# SCH_WHITEBoard_ESP32_S2_Saola_2021-06-30.net
KiCad netlist of a schematic drawn in EasyEDA
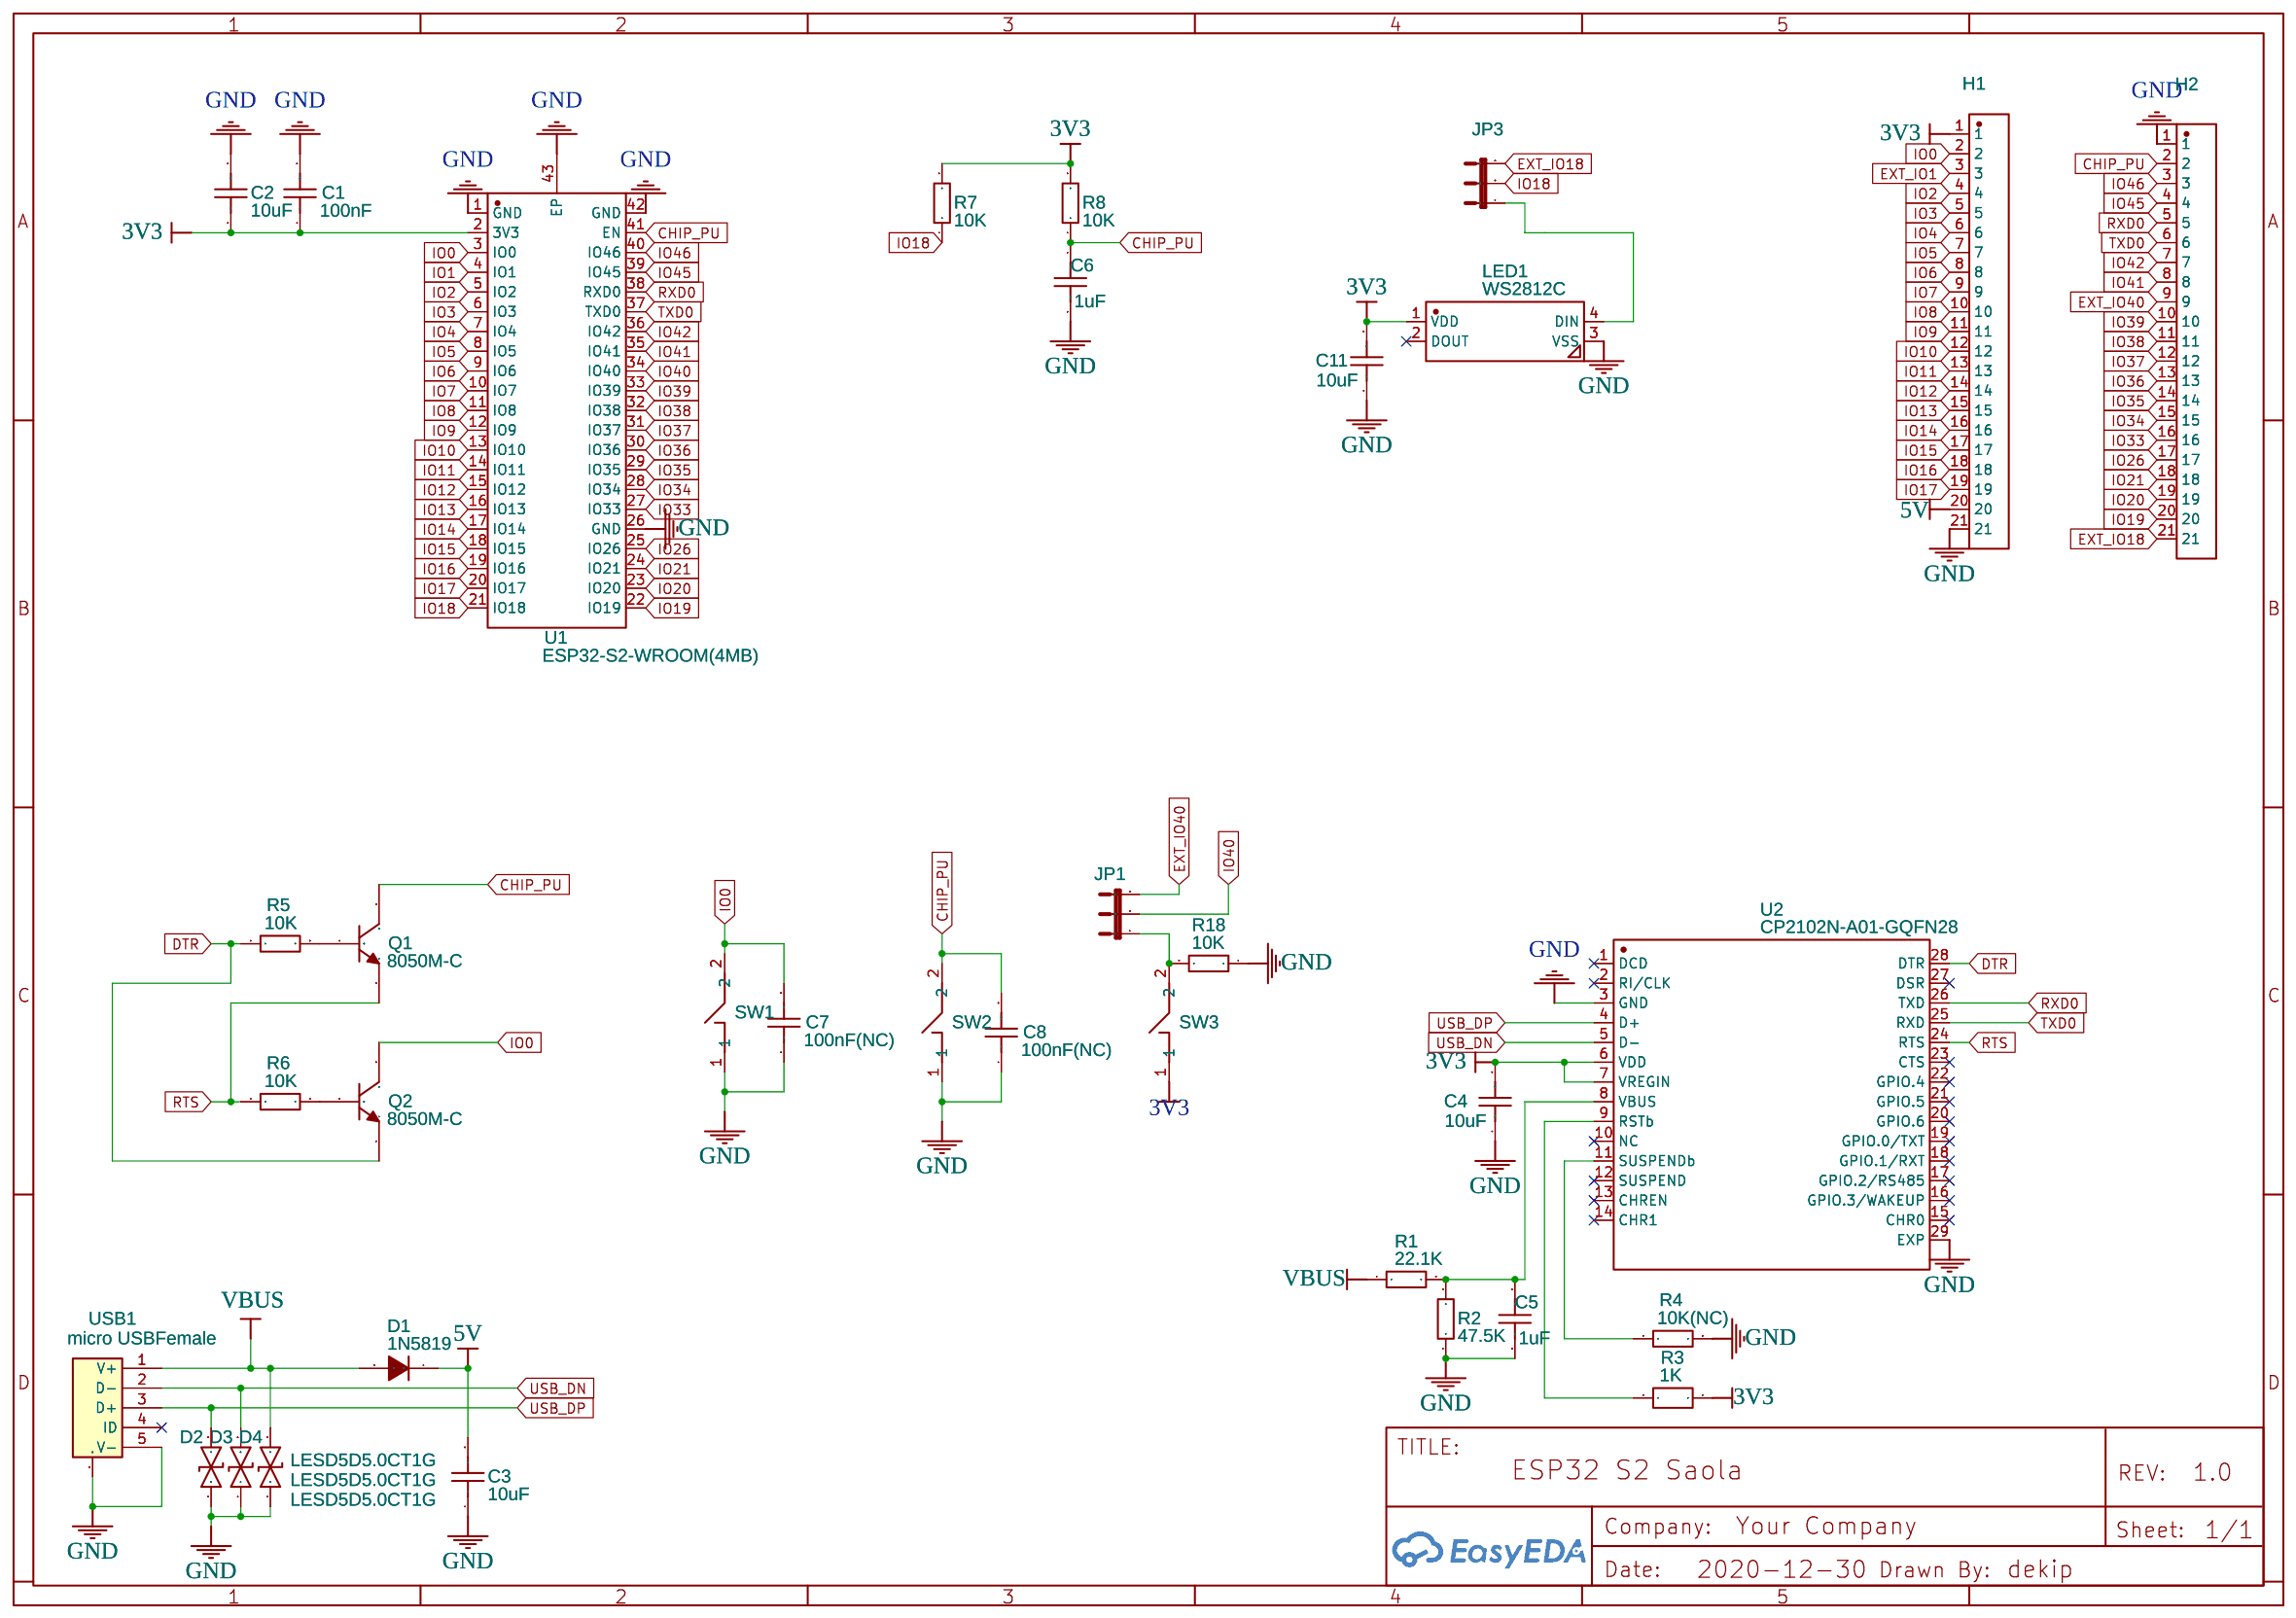
[diagram p0: Sheet_1]
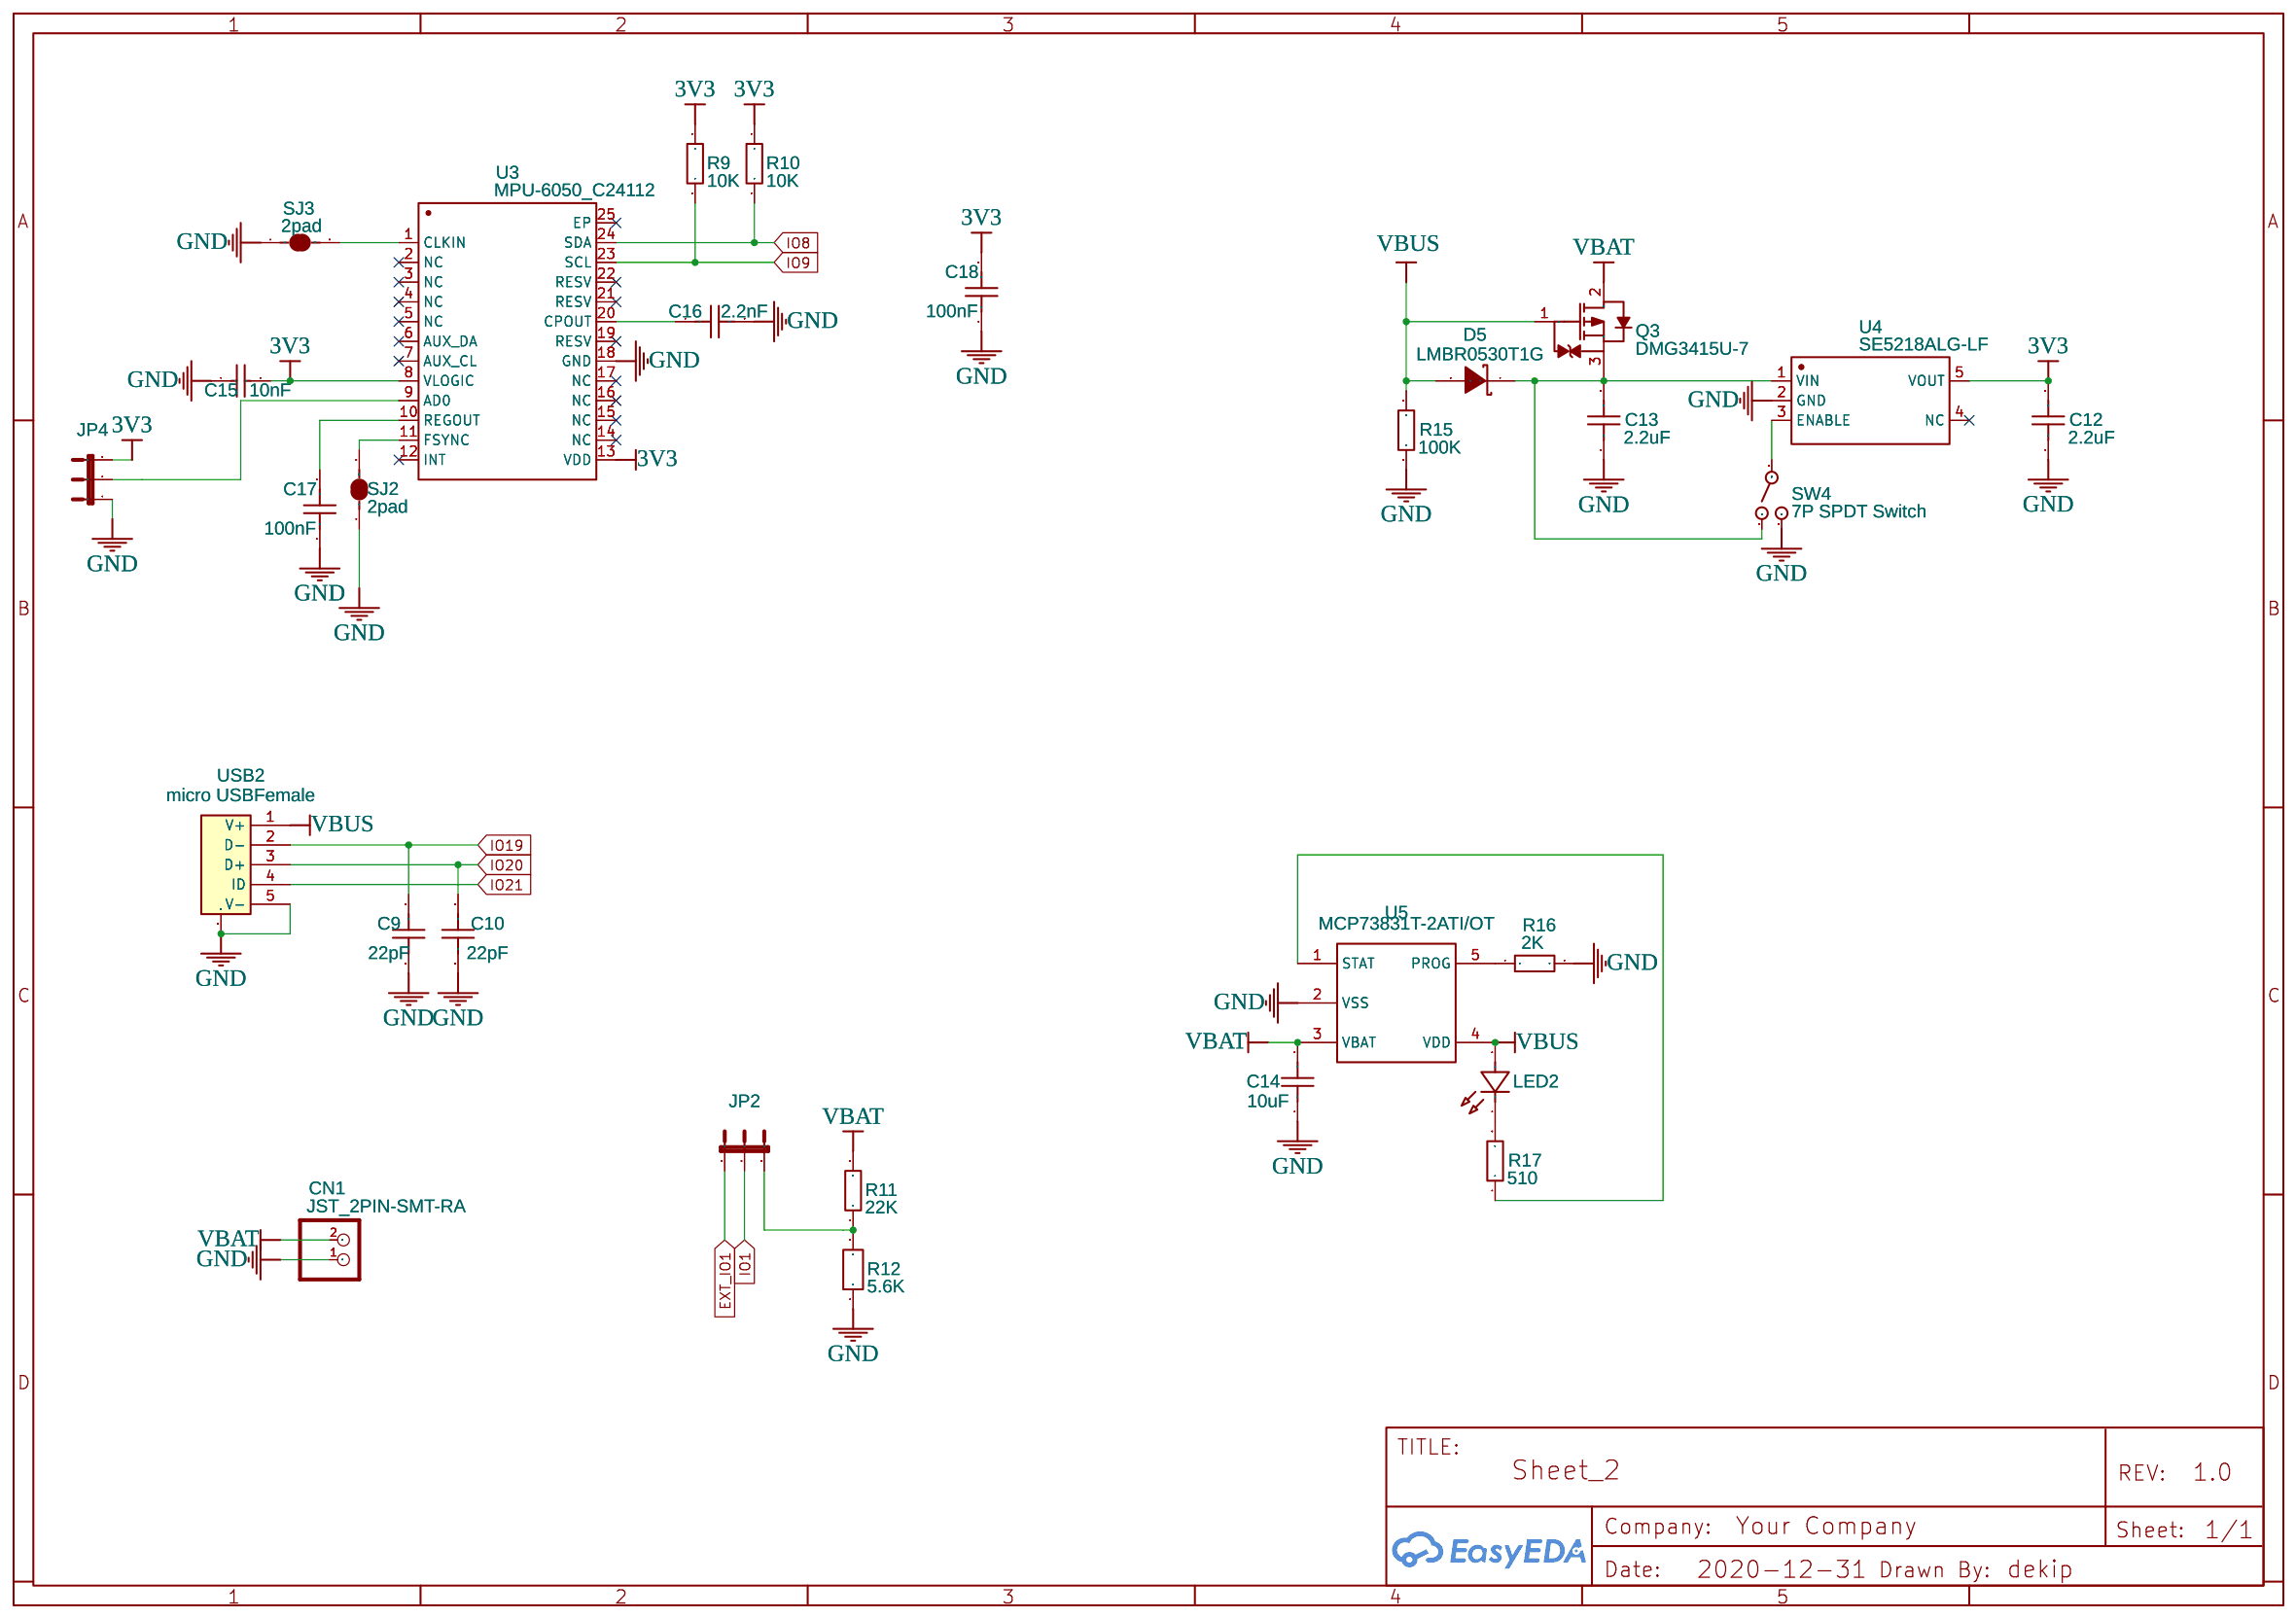
[diagram p1: Sheet_2]

(export (version "E")
  (design (tool "Eeschema 10.0.6"))
  (components
    (comp (ref "C1")
      (value "100nF")
      (fields
        (field (name "BOM_Manufacturer Part") "C0805C104J5RAC7800")
        (field (name "BOM_Supplier Part") "C599848")
      )
      (libsource (lib "") (part "C0805C104J5RAC7800"))
    )
    (comp (ref "C2")
      (value "10uF")
      (fields
        (field (name "BOM_Manufacturer Part") "C0805X106K010T")
        (field (name "BOM_Supplier Part") "C340314")
      )
      (libsource (lib "") (part "C0805X106K010T"))
    )
    (comp (ref "C3")
      (value "10uF")
      (fields
        (field (name "BOM_Manufacturer Part") "C0805X106K010T")
        (field (name "BOM_Supplier Part") "C340314")
      )
      (libsource (lib "") (part "C0805X106K010T"))
    )
    (comp (ref "C4")
      (value "10uF")
      (fields
        (field (name "BOM_Manufacturer Part") "C0805X106K010T")
        (field (name "BOM_Supplier Part") "C340314")
      )
      (libsource (lib "") (part "C0805X106K010T"))
    )
    (comp (ref "C5")
      (value "1uF")
      (fields
        (field (name "BOM_Manufacturer Part") "C0805X105K050T")
        (field (name "BOM_Supplier Part") "C340303")
      )
      (libsource (lib "") (part "C0805X105K050T"))
    )
    (comp (ref "C6")
      (value "1uF")
      (fields
        (field (name "BOM_Manufacturer Part") "C0805X105K050T")
        (field (name "BOM_Supplier Part") "C340303")
      )
      (libsource (lib "") (part "C0805X105K050T"))
    )
    (comp (ref "C7")
      (value "100nF(NC)")
      (fields
        (field (name "BOM_Manufacturer Part") "C0805C104J5RAC7800")
        (field (name "BOM_Supplier Part") "C599848")
      )
      (libsource (lib "") (part "C0805C104J5RAC7800"))
    )
    (comp (ref "C8")
      (value "100nF(NC)")
      (fields
        (field (name "BOM_Manufacturer Part") "C0805C104J5RAC7800")
        (field (name "BOM_Supplier Part") "C599848")
      )
      (libsource (lib "") (part "C0805C104J5RAC7800"))
    )
    (comp (ref "C11")
      (value "10uF")
      (fields
        (field (name "BOM_Manufacturer Part") "C0805X106K010T")
        (field (name "BOM_Supplier Part") "C340314")
      )
      (libsource (lib "") (part "C0805X106K010T"))
    )
    (comp (ref "D1")
      (value "1N5819")
      (fields
        (field (name "BOM_Manufacturer Part") "1N5819HW1-7-F")
        (field (name "BOM_Supplier Part") "C117948")
      )
      (libsource (lib "") (part "1N5819HW1-7-F"))
    )
    (comp (ref "D2")
      (value "LESD5D5.0CT1G")
      (fields (field (name "BOM_Supplier Part") "C383211"))
      (libsource (lib "") (part "LESD5D5.0CT1G"))
    )
    (comp (ref "D3")
      (value "LESD5D5.0CT1G")
      (fields (field (name "BOM_Supplier Part") "C383211"))
      (libsource (lib "") (part "LESD5D5.0CT1G"))
    )
    (comp (ref "D4")
      (value "LESD5D5.0CT1G")
      (fields (field (name "BOM_Supplier Part") "C383211"))
      (libsource (lib "") (part "LESD5D5.0CT1G"))
    )
    (comp (ref "H1")
      (value "X6511WV-21H-C30D60")
      (fields (field (name "BOM_Supplier Part") "C725953"))
      (libsource (lib "") (part "X6511WV-21H-C30D60"))
    )
    (comp (ref "H2")
      (value "X6511WV-21H-C30D60")
      (fields (field (name "BOM_Supplier Part") "C725953"))
      (libsource (lib "") (part "X6511WV-21H-C30D60"))
    )
    (comp (ref "JP1") (value "JUMPER-3SMD") (libsource (lib "") (part "JUMPER-3SMD")))
    (comp (ref "JP3") (value "JUMPER-3SMD") (libsource (lib "") (part "JUMPER-3SMD")))
    (comp (ref "LED1")
      (value "WS2812C")
      (fields (field (name "BOM_Supplier Part") "C114587"))
      (libsource (lib "") (part "WS2812C"))
    )
    (comp (ref "Q1")
      (value "8050M-C")
      (fields (field (name "BOM_Supplier Part") "C305454"))
      (libsource (lib "") (part "8050M-C"))
    )
    (comp (ref "Q2")
      (value "8050M-C")
      (fields (field (name "BOM_Supplier Part") "C305454"))
      (libsource (lib "") (part "8050M-C"))
    )
    (comp (ref "R1")
      (value "22.1K")
      (fields
        (field (name "BOM_Manufacturer Part") "CR0805-FX-2212ELF")
        (field (name "BOM_Supplier Part") "C204311")
      )
      (libsource (lib "") (part "CR0805-FX-2212ELF"))
    )
    (comp (ref "R2")
      (value "47.5K")
      (fields
        (field (name "BOM_Manufacturer Part") "AR05DTCW4752")
        (field (name "BOM_Supplier Part") "C319613")
      )
      (libsource (lib "") (part "AR05DTCW4752"))
    )
    (comp (ref "R3")
      (value "1K")
      (fields
        (field (name "BOM_Manufacturer Part") "ERJPB6B1001V")
        (field (name "BOM_Supplier Part") "C413712")
      )
      (libsource (lib "") (part "ERJPB6B1001V"))
    )
    (comp (ref "R4")
      (value "10K(NC)")
      (fields
        (field (name "BOM_Manufacturer Part") "RN73H2ATTD1002B25")
        (field (name "BOM_Supplier Part") "C186277")
      )
      (libsource (lib "") (part "RN73H2ATTD1002B25"))
    )
    (comp (ref "R5")
      (value "10K")
      (fields
        (field (name "BOM_Manufacturer Part") "RN73H2ATTD1002B25")
        (field (name "BOM_Supplier Part") "C186277")
      )
      (libsource (lib "") (part "RN73H2ATTD1002B25"))
    )
    (comp (ref "R6")
      (value "10K")
      (fields
        (field (name "BOM_Manufacturer Part") "RN73H2ATTD1002B25")
        (field (name "BOM_Supplier Part") "C186277")
      )
      (libsource (lib "") (part "RN73H2ATTD1002B25"))
    )
    (comp (ref "R7")
      (value "10K")
      (fields
        (field (name "BOM_Manufacturer Part") "RN73H2ATTD1002B25")
        (field (name "BOM_Supplier Part") "C186277")
      )
      (libsource (lib "") (part "RN73H2ATTD1002B25_2"))
    )
    (comp (ref "R8")
      (value "10K")
      (fields
        (field (name "BOM_Manufacturer Part") "RN73H2ATTD1002B25")
        (field (name "BOM_Supplier Part") "C186277")
      )
      (libsource (lib "") (part "RN73H2ATTD1002B25_2"))
    )
    (comp (ref "R18")
      (value "10K")
      (fields
        (field (name "BOM_Manufacturer Part") "RN73H2ATTD1002B25")
        (field (name "BOM_Supplier Part") "C186277")
      )
      (libsource (lib "") (part "RN73H2ATTD1002B25_1"))
    )
    (comp (ref "SW1")
      (value "1TS002B-1900-4300")
      (fields (field (name "BOM_Supplier Part") "C318823"))
      (libsource (lib "") (part "1TS002B-1900-4300"))
    )
    (comp (ref "SW2")
      (value "1TS002B-1900-4300")
      (fields (field (name "BOM_Supplier Part") "C318823"))
      (libsource (lib "") (part "1TS002B-1900-4300"))
    )
    (comp (ref "SW3")
      (value "1TS002B-1900-4300")
      (fields (field (name "BOM_Supplier Part") "C318823"))
      (libsource (lib "") (part "1TS002B-1900-4300"))
    )
    (comp (ref "U1")
      (value "ESP32-S2-WROOM(4MB)")
      (fields (field (name "BOM_Supplier Part") "C701327"))
      (libsource (lib "") (part "ESP32-S2-WROOM(4MB)"))
    )
    (comp (ref "U2")
      (value "CP2102N-A01-GQFN28")
      (fields (field (name "BOM_Supplier Part") "C105167"))
      (libsource (lib "") (part "CP2102N-A01-GQFN28"))
    )
    (comp (ref "USB1")
      (value "micro USBFemale")
      (fields (field (name "BOM_Supplier Part") "C10418"))
      (libsource (lib "") (part "micro USBFemale"))
    )
    (comp (ref "C9")
      (value "22pF")
      (fields
        (field (name "BOM_Manufacturer Part") "C0805C220K5RACAUTO")
        (field (name "BOM_Supplier Part") "C129647")
      )
      (libsource (lib "") (part "C0805C220K5RACAUTO"))
    )
    (comp (ref "C10")
      (value "22pF")
      (fields
        (field (name "BOM_Manufacturer Part") "C0805C220K5RACAUTO")
        (field (name "BOM_Supplier Part") "C129647")
      )
      (libsource (lib "") (part "C0805C220K5RACAUTO"))
    )
    (comp (ref "C12")
      (value "2.2uF")
      (fields
        (field (name "BOM_Manufacturer Part") "CC0805MRY5V7BB225")
        (field (name "BOM_Supplier Part") "C527243")
      )
      (libsource (lib "") (part "CC0805MRY5V7BB225"))
    )
    (comp (ref "C13")
      (value "2.2uF")
      (fields
        (field (name "BOM_Manufacturer Part") "CC0805MRY5V7BB225")
        (field (name "BOM_Supplier Part") "C527243")
      )
      (libsource (lib "") (part "CC0805MRY5V7BB225"))
    )
    (comp (ref "C14")
      (value "10uF")
      (fields
        (field (name "BOM_Manufacturer Part") "C0805X106K010T")
        (field (name "BOM_Supplier Part") "C340314")
      )
      (libsource (lib "") (part "C0805X106K010T"))
    )
    (comp (ref "C15")
      (value "10nF")
      (fields
        (field (name "BOM_Manufacturer Part") "C0805X103K201T")
        (field (name "BOM_Supplier Part") "C105948")
      )
      (libsource (lib "") (part "C0805X103K201T"))
    )
    (comp (ref "C16")
      (value "2.2nF")
      (fields
        (field (name "BOM_Manufacturer Part") "C0805X222K501T")
        (field (name "BOM_Supplier Part") "C340306")
      )
      (libsource (lib "") (part "C0805X222K501T"))
    )
    (comp (ref "C17")
      (value "100nF")
      (fields
        (field (name "BOM_Manufacturer Part") "C0805C104J5RAC7800")
        (field (name "BOM_Supplier Part") "C599848")
      )
      (libsource (lib "") (part "C0805C104J5RAC7800"))
    )
    (comp (ref "C18")
      (value "100nF")
      (fields
        (field (name "BOM_Manufacturer Part") "C0805C104J5RAC7800")
        (field (name "BOM_Supplier Part") "C599848")
      )
      (libsource (lib "") (part "C0805C104J5RAC7800"))
    )
    (comp (ref "CN1") (value "JST_2PIN-SMT-RA") (libsource (lib "") (part "JST_2PIN-SMT-RA")))
    (comp (ref "D5")
      (value "LMBR0530T1G")
      (fields (field (name "BOM_Supplier Part") "C18863"))
      (libsource (lib "") (part "LMBR0530T1G"))
    )
    (comp (ref "JP2") (value "JUMPER-3SMD") (libsource (lib "") (part "JUMPER-3SMD_1")))
    (comp (ref "JP4") (value "JUMPER-3SMD") (libsource (lib "") (part "JUMPER-3SMD")))
    (comp (ref "LED2")
      (value "GBD-C171KSKT-DZ")
      (fields (field (name "BOM_Supplier Part") "C712082"))
      (libsource (lib "") (part "GBD-C171KSKT-DZ"))
    )
    (comp (ref "Q3")
      (value "DMG3415U-7")
      (fields (field (name "BOM_Supplier Part") "C96616"))
      (libsource (lib "") (part "DMG3415U-7"))
    )
    (comp (ref "R9")
      (value "10K")
      (fields
        (field (name "BOM_Manufacturer Part") "RN73H2ATTD1002B25")
        (field (name "BOM_Supplier Part") "C186277")
      )
      (libsource (lib "") (part "RN73H2ATTD1002B25"))
    )
    (comp (ref "R10")
      (value "10K")
      (fields
        (field (name "BOM_Manufacturer Part") "RN73H2ATTD1002B25")
        (field (name "BOM_Supplier Part") "C186277")
      )
      (libsource (lib "") (part "RN73H2ATTD1002B25"))
    )
    (comp (ref "R11")
      (value "22K")
      (fields
        (field (name "BOM_Manufacturer Part") "0805W8F2202T5E")
        (field (name "BOM_Supplier Part") "C17560")
      )
      (libsource (lib "") (part "0805W8F2202T5E"))
    )
    (comp (ref "R12")
      (value "5.6K")
      (fields
        (field (name "BOM_Manufacturer Part") "ERJ6GEYJ562V")
        (field (name "BOM_Supplier Part") "C413194")
      )
      (libsource (lib "") (part "ERJ6GEYJ562V"))
    )
    (comp (ref "R15")
      (value "100K")
      (fields
        (field (name "BOM_Manufacturer Part") "ERJ6RBD1003V")
        (field (name "BOM_Supplier Part") "C336855")
      )
      (libsource (lib "") (part "ERJ6RBD1003V"))
    )
    (comp (ref "R16")
      (value "2K")
      (fields
        (field (name "BOM_Manufacturer Part") "RMS10FT2001")
        (field (name "BOM_Supplier Part") "C212356")
      )
      (libsource (lib "") (part "RMS10FT2001"))
    )
    (comp (ref "R17")
      (value "510")
      (fields
        (field (name "BOM_Manufacturer Part") "RMC08055105%N")
        (field (name "BOM_Supplier Part") "C269737")
      )
      (libsource (lib "") (part "RMC08055105%N"))
    )
    (comp (ref "SJ2") (value "2pad") (libsource (lib "") (part "SOLDERJUMPER-OLDTRACE")))
    (comp (ref "SJ3") (value "2pad") (libsource (lib "") (part "SOLDERJUMPER-OLDTRACE_1")))
    (comp (ref "SW4")
      (value "7P SPDT Switch")
      (fields (field (name "BOM_Manufacturer Part") "MSK12C02") (field (name "BOM_Supplier Part") "C431540"))
      (libsource (lib "") (part "7P SPDT Switch"))
    )
    (comp (ref "U3")
      (value "MPU-6050_C24112")
      (fields (field (name "BOM_Manufacturer Part") "MPU-6050") (field (name "BOM_Supplier Part") "C24112"))
      (libsource (lib "") (part "MPU-6050_C24112"))
    )
    (comp (ref "U4")
      (value "SE5218ALG-LF")
      (fields (field (name "BOM_Supplier Part") "C118233"))
      (libsource (lib "") (part "SE5218ALG-LF"))
    )
    (comp (ref "U5")
      (value "MCP73831T-2ATI/OT")
      (fields (field (name "BOM_Supplier Part") "C14879"))
      (libsource (lib "") (part "MCP73831T-2ATI/OT"))
    )
    (comp (ref "USB2")
      (value "micro USBFemale")
      (fields (field (name "BOM_Supplier Part") "C10418"))
      (libsource (lib "") (part "micro USBFemale"))
    )
  )
  (nets
    (net (code "1") (name "3V3") (class "Default")
      (node (ref "C1") (pin "1") (pinfunction "1_1") (pintype "unspecified"))
      (node (ref "C11") (pin "2") (pinfunction "2_2") (pintype "unspecified"))
      (node (ref "C12") (pin "2") (pinfunction "2_2") (pintype "unspecified"))
      (node (ref "C15") (pin "2") (pinfunction "2_2") (pintype "input"))
      (node (ref "C18") (pin "2") (pinfunction "2_2") (pintype "unspecified"))
      (node (ref "C2") (pin "1") (pinfunction "1_1") (pintype "unspecified"))
      (node (ref "C4") (pin "2") (pinfunction "2_2") (pintype "unspecified"))
      (node (ref "H1") (pin "1") (pinfunction "1_1") (pintype "unspecified"))
      (node (ref "JP4") (pin "3") (pinfunction "3_3") (pintype "unspecified"))
      (node (ref "LED1") (pin "1") (pinfunction "VDD_1") (pintype "unspecified"))
      (node (ref "R10") (pin "1") (pinfunction "1_1") (pintype "unspecified"))
      (node (ref "R3") (pin "2") (pinfunction "2_2") (pintype "unspecified"))
      (node (ref "R7") (pin "2") (pinfunction "2_2") (pintype "unspecified"))
      (node (ref "R8") (pin "2") (pinfunction "2_2") (pintype "unspecified"))
      (node (ref "R9") (pin "1") (pinfunction "1_1") (pintype "unspecified"))
      (node (ref "SW3") (pin "1") (pinfunction "1_1") (pintype "unspecified"))
      (node (ref "U1") (pin "2") (pinfunction "3V3_2") (pintype "unspecified"))
      (node (ref "U2") (pin "6") (pinfunction "VDD_6") (pintype "unspecified"))
      (node (ref "U2") (pin "7") (pinfunction "VREGIN_7") (pintype "unspecified"))
      (node (ref "U3") (pin "13") (pinfunction "VDD_13") (pintype "unspecified"))
      (node (ref "U3") (pin "8") (pinfunction "VLOGIC_8") (pintype "unspecified"))
      (node (ref "U4") (pin "5") (pinfunction "VOUT_5") (pintype "unspecified"))
    )
    (net (code "2") (name "5V") (class "Default")
      (node (ref "C3") (pin "2") (pinfunction "2_2") (pintype "unspecified"))
      (node (ref "D1") (pin "1") (pinfunction "K_1") (pintype "unspecified"))
      (node (ref "H1") (pin "20") (pinfunction "20_20") (pintype "unspecified"))
    )
    (net (code "3") (name "CHIP_PU") (class "Default")
      (node (ref "C6") (pin "1") (pinfunction "1_1") (pintype "unspecified"))
      (node (ref "C8") (pin "2") (pinfunction "2_2") (pintype "unspecified"))
      (node (ref "H2") (pin "2") (pinfunction "2_2") (pintype "unspecified"))
      (node (ref "Q1") (pin "3") (pinfunction "C_3") (pintype "unspecified"))
      (node (ref "R8") (pin "1") (pinfunction "1_1") (pintype "unspecified"))
      (node (ref "SW2") (pin "2") (pinfunction "2_2") (pintype "unspecified"))
      (node (ref "U1") (pin "41") (pinfunction "EN_41") (pintype "unspecified"))
    )
    (net (code "4") (name "DTR") (class "Default")
      (node (ref "Q2") (pin "2") (pinfunction "E_2") (pintype "unspecified"))
      (node (ref "R5") (pin "1") (pinfunction "1_1") (pintype "unspecified"))
      (node (ref "U2") (pin "28") (pinfunction "DTR_28") (pintype "unspecified"))
    )
    (net (code "5") (name "EXT_IO1") (class "Default")
      (node (ref "H1") (pin "3") (pinfunction "3_3") (pintype "unspecified"))
      (node (ref "JP2") (pin "1") (pinfunction "1_1") (pintype "unspecified"))
    )
    (net (code "6") (name "EXT_IO18") (class "Default")
      (node (ref "H2") (pin "21") (pinfunction "21_21") (pintype "unspecified"))
      (node (ref "JP3") (pin "3") (pinfunction "3_3") (pintype "unspecified"))
    )
    (net (code "7") (name "EXT_IO40") (class "Default")
      (node (ref "H2") (pin "9") (pinfunction "9_9") (pintype "unspecified"))
      (node (ref "JP1") (pin "3") (pinfunction "3_3") (pintype "unspecified"))
    )
    (net (code "8") (name "GND") (class "Default")
      (node (ref "C1") (pin "2") (pinfunction "2_2") (pintype "unspecified"))
      (node (ref "C10") (pin "2") (pinfunction "2_2") (pintype "unspecified"))
      (node (ref "C11") (pin "1") (pinfunction "1_1") (pintype "unspecified"))
      (node (ref "C12") (pin "1") (pinfunction "1_1") (pintype "unspecified"))
      (node (ref "C13") (pin "1") (pinfunction "1_1") (pintype "unspecified"))
      (node (ref "C14") (pin "1") (pinfunction "1_1") (pintype "unspecified"))
      (node (ref "C15") (pin "1") (pinfunction "1_1") (pintype "input"))
      (node (ref "C16") (pin "2") (pinfunction "2_2") (pintype "unspecified"))
      (node (ref "C17") (pin "1") (pinfunction "1_1") (pintype "unspecified"))
      (node (ref "C18") (pin "1") (pinfunction "1_1") (pintype "unspecified"))
      (node (ref "C2") (pin "2") (pinfunction "2_2") (pintype "unspecified"))
      (node (ref "C3") (pin "1") (pinfunction "1_1") (pintype "unspecified"))
      (node (ref "C4") (pin "1") (pinfunction "1_1") (pintype "unspecified"))
      (node (ref "C5") (pin "2") (pinfunction "2_2") (pintype "unspecified"))
      (node (ref "C6") (pin "2") (pinfunction "2_2") (pintype "unspecified"))
      (node (ref "C7") (pin "1") (pinfunction "1_1") (pintype "unspecified"))
      (node (ref "C8") (pin "1") (pinfunction "1_1") (pintype "unspecified"))
      (node (ref "C9") (pin "2") (pinfunction "2_2") (pintype "unspecified"))
      (node (ref "CN1") (pin "1") (pinfunction "2_1") (pintype "unspecified"))
      (node (ref "D2") (pin "1") (pinfunction "1_1") (pintype "unspecified"))
      (node (ref "D3") (pin "1") (pinfunction "1_1") (pintype "unspecified"))
      (node (ref "D4") (pin "1") (pinfunction "1_1") (pintype "unspecified"))
      (node (ref "H1") (pin "21") (pinfunction "21_21") (pintype "unspecified"))
      (node (ref "H2") (pin "1") (pinfunction "1_1") (pintype "unspecified"))
      (node (ref "JP4") (pin "1") (pinfunction "1_1") (pintype "unspecified"))
      (node (ref "LED1") (pin "3") (pinfunction "VSS_3") (pintype "unspecified"))
      (node (ref "R12") (pin "1") (pinfunction "1_1") (pintype "unspecified"))
      (node (ref "R15") (pin "1") (pinfunction "1_1") (pintype "unspecified"))
      (node (ref "R16") (pin "2") (pinfunction "2_2") (pintype "unspecified"))
      (node (ref "R18") (pin "1") (pinfunction "1_1") (pintype "unspecified"))
      (node (ref "R2") (pin "1") (pinfunction "1_1") (pintype "unspecified"))
      (node (ref "R4") (pin "2") (pinfunction "2_2") (pintype "unspecified"))
      (node (ref "SJ2") (pin "1") (pinfunction "1_1") (pintype "unspecified"))
      (node (ref "SJ3") (pin "1") (pinfunction "1_1") (pintype "unspecified"))
      (node (ref "SW1") (pin "1") (pinfunction "1_1") (pintype "unspecified"))
      (node (ref "SW2") (pin "1") (pinfunction "1_1") (pintype "unspecified"))
      (node (ref "SW4") (pin "1") (pinfunction "1_1") (pintype "unspecified"))
      (node (ref "U1") (pin "1") (pinfunction "GND_1") (pintype "unspecified"))
      (node (ref "U1") (pin "26") (pinfunction "GND_26") (pintype "unspecified"))
      (node (ref "U1") (pin "42") (pinfunction "GND_42") (pintype "unspecified"))
      (node (ref "U1") (pin "43") (pinfunction "EP_43") (pintype "unspecified"))
      (node (ref "U2") (pin "29") (pinfunction "EXP_29") (pintype "unspecified"))
      (node (ref "U2") (pin "3") (pinfunction "GND_3") (pintype "unspecified"))
      (node (ref "U3") (pin "18") (pinfunction "GND_18") (pintype "unspecified"))
      (node (ref "U4") (pin "2") (pinfunction "GND_2") (pintype "unspecified"))
      (node (ref "U5") (pin "2") (pinfunction "VSS_2") (pintype "unspecified"))
      (node (ref "USB1") (pin "0") (pinfunction "MTN_0") (pintype "input"))
      (node (ref "USB1") (pin "5") (pinfunction "V-_5") (pintype "unspecified"))
      (node (ref "USB2") (pin "0") (pinfunction "MTN_0") (pintype "input"))
      (node (ref "USB2") (pin "5") (pinfunction "V-_5") (pintype "unspecified"))
    )
    (net (code "9") (name "IO0") (class "Default")
      (node (ref "C7") (pin "2") (pinfunction "2_2") (pintype "unspecified"))
      (node (ref "H1") (pin "2") (pinfunction "2_2") (pintype "unspecified"))
      (node (ref "Q2") (pin "3") (pinfunction "C_3") (pintype "unspecified"))
      (node (ref "SW1") (pin "2") (pinfunction "2_2") (pintype "unspecified"))
      (node (ref "U1") (pin "3") (pinfunction "IO0_3") (pintype "unspecified"))
    )
    (net (code "10") (name "IO1") (class "Default")
      (node (ref "JP2") (pin "2") (pinfunction "2_2") (pintype "unspecified"))
      (node (ref "U1") (pin "4") (pinfunction "IO1_4") (pintype "unspecified"))
    )
    (net (code "11") (name "IO2") (class "Default")
      (node (ref "H1") (pin "4") (pinfunction "4_4") (pintype "unspecified"))
      (node (ref "U1") (pin "5") (pinfunction "IO2_5") (pintype "unspecified"))
    )
    (net (code "12") (name "IO3") (class "Default")
      (node (ref "H1") (pin "5") (pinfunction "5_5") (pintype "unspecified"))
      (node (ref "U1") (pin "6") (pinfunction "IO3_6") (pintype "unspecified"))
    )
    (net (code "13") (name "IO4") (class "Default")
      (node (ref "H1") (pin "6") (pinfunction "6_6") (pintype "unspecified"))
      (node (ref "U1") (pin "7") (pinfunction "IO4_7") (pintype "unspecified"))
    )
    (net (code "14") (name "IO5") (class "Default")
      (node (ref "H1") (pin "7") (pinfunction "7_7") (pintype "unspecified"))
      (node (ref "U1") (pin "8") (pinfunction "IO5_8") (pintype "unspecified"))
    )
    (net (code "15") (name "IO6") (class "Default")
      (node (ref "H1") (pin "8") (pinfunction "8_8") (pintype "unspecified"))
      (node (ref "U1") (pin "9") (pinfunction "IO6_9") (pintype "unspecified"))
    )
    (net (code "16") (name "IO7") (class "Default")
      (node (ref "H1") (pin "9") (pinfunction "9_9") (pintype "unspecified"))
      (node (ref "U1") (pin "10") (pinfunction "IO7_10") (pintype "unspecified"))
    )
    (net (code "17") (name "IO8") (class "Default")
      (node (ref "H1") (pin "10") (pinfunction "10_10") (pintype "unspecified"))
      (node (ref "R10") (pin "2") (pinfunction "2_2") (pintype "unspecified"))
      (node (ref "U1") (pin "11") (pinfunction "IO8_11") (pintype "unspecified"))
      (node (ref "U3") (pin "24") (pinfunction "SDA_24") (pintype "unspecified"))
    )
    (net (code "18") (name "IO9") (class "Default")
      (node (ref "H1") (pin "11") (pinfunction "11_11") (pintype "unspecified"))
      (node (ref "R9") (pin "2") (pinfunction "2_2") (pintype "unspecified"))
      (node (ref "U1") (pin "12") (pinfunction "IO9_12") (pintype "unspecified"))
      (node (ref "U3") (pin "23") (pinfunction "SCL_23") (pintype "unspecified"))
    )
    (net (code "19") (name "IO10") (class "Default")
      (node (ref "H1") (pin "12") (pinfunction "12_12") (pintype "unspecified"))
      (node (ref "U1") (pin "13") (pinfunction "IO10_13") (pintype "unspecified"))
    )
    (net (code "20") (name "IO11") (class "Default")
      (node (ref "H1") (pin "13") (pinfunction "13_13") (pintype "unspecified"))
      (node (ref "U1") (pin "14") (pinfunction "IO11_14") (pintype "unspecified"))
    )
    (net (code "21") (name "IO12") (class "Default")
      (node (ref "H1") (pin "14") (pinfunction "14_14") (pintype "unspecified"))
      (node (ref "U1") (pin "15") (pinfunction "IO12_15") (pintype "unspecified"))
    )
    (net (code "22") (name "IO13") (class "Default")
      (node (ref "H1") (pin "15") (pinfunction "15_15") (pintype "unspecified"))
      (node (ref "U1") (pin "16") (pinfunction "IO13_16") (pintype "unspecified"))
    )
    (net (code "23") (name "IO14") (class "Default")
      (node (ref "H1") (pin "16") (pinfunction "16_16") (pintype "unspecified"))
      (node (ref "U1") (pin "17") (pinfunction "IO14_17") (pintype "unspecified"))
    )
    (net (code "24") (name "IO15") (class "Default")
      (node (ref "H1") (pin "17") (pinfunction "17_17") (pintype "unspecified"))
      (node (ref "U1") (pin "18") (pinfunction "IO15_18") (pintype "unspecified"))
    )
    (net (code "25") (name "IO16") (class "Default")
      (node (ref "H1") (pin "18") (pinfunction "18_18") (pintype "unspecified"))
      (node (ref "U1") (pin "19") (pinfunction "IO16_19") (pintype "unspecified"))
    )
    (net (code "26") (name "IO17") (class "Default")
      (node (ref "H1") (pin "19") (pinfunction "19_19") (pintype "unspecified"))
      (node (ref "U1") (pin "20") (pinfunction "IO17_20") (pintype "unspecified"))
    )
    (net (code "27") (name "IO18") (class "Default")
      (node (ref "JP3") (pin "2") (pinfunction "2_2") (pintype "unspecified"))
      (node (ref "R7") (pin "1") (pinfunction "1_1") (pintype "unspecified"))
      (node (ref "U1") (pin "21") (pinfunction "IO18_21") (pintype "unspecified"))
    )
    (net (code "28") (name "IO19") (class "Default")
      (node (ref "C9") (pin "1") (pinfunction "1_1") (pintype "unspecified"))
      (node (ref "H2") (pin "20") (pinfunction "20_20") (pintype "unspecified"))
      (node (ref "U1") (pin "22") (pinfunction "IO19_22") (pintype "unspecified"))
      (node (ref "USB2") (pin "2") (pinfunction "D-_2") (pintype "unspecified"))
    )
    (net (code "29") (name "IO20") (class "Default")
      (node (ref "C10") (pin "1") (pinfunction "1_1") (pintype "unspecified"))
      (node (ref "H2") (pin "19") (pinfunction "19_19") (pintype "unspecified"))
      (node (ref "U1") (pin "23") (pinfunction "IO20_23") (pintype "unspecified"))
      (node (ref "USB2") (pin "3") (pinfunction "D+_3") (pintype "unspecified"))
    )
    (net (code "30") (name "IO21") (class "Default")
      (node (ref "H2") (pin "18") (pinfunction "18_18") (pintype "unspecified"))
      (node (ref "U1") (pin "24") (pinfunction "IO21_24") (pintype "unspecified"))
      (node (ref "USB2") (pin "4") (pinfunction "ID_4") (pintype "unspecified"))
    )
    (net (code "31") (name "IO26") (class "Default")
      (node (ref "H2") (pin "17") (pinfunction "17_17") (pintype "unspecified"))
      (node (ref "U1") (pin "25") (pinfunction "IO26_25") (pintype "unspecified"))
    )
    (net (code "32") (name "IO33") (class "Default")
      (node (ref "H2") (pin "16") (pinfunction "16_16") (pintype "unspecified"))
      (node (ref "U1") (pin "27") (pinfunction "IO33_27") (pintype "unspecified"))
    )
    (net (code "33") (name "IO34") (class "Default")
      (node (ref "H2") (pin "15") (pinfunction "15_15") (pintype "unspecified"))
      (node (ref "U1") (pin "28") (pinfunction "IO34_28") (pintype "unspecified"))
    )
    (net (code "34") (name "IO35") (class "Default")
      (node (ref "H2") (pin "14") (pinfunction "14_14") (pintype "unspecified"))
      (node (ref "U1") (pin "29") (pinfunction "IO35_29") (pintype "unspecified"))
    )
    (net (code "35") (name "IO36") (class "Default")
      (node (ref "H2") (pin "13") (pinfunction "13_13") (pintype "unspecified"))
      (node (ref "U1") (pin "30") (pinfunction "IO36_30") (pintype "unspecified"))
    )
    (net (code "36") (name "IO37") (class "Default")
      (node (ref "H2") (pin "12") (pinfunction "12_12") (pintype "unspecified"))
      (node (ref "U1") (pin "31") (pinfunction "IO37_31") (pintype "unspecified"))
    )
    (net (code "37") (name "IO38") (class "Default")
      (node (ref "H2") (pin "11") (pinfunction "11_11") (pintype "unspecified"))
      (node (ref "U1") (pin "32") (pinfunction "IO38_32") (pintype "unspecified"))
    )
    (net (code "38") (name "IO39") (class "Default")
      (node (ref "H2") (pin "10") (pinfunction "10_10") (pintype "unspecified"))
      (node (ref "U1") (pin "33") (pinfunction "IO39_33") (pintype "unspecified"))
    )
    (net (code "39") (name "IO40") (class "Default")
      (node (ref "JP1") (pin "2") (pinfunction "2_2") (pintype "unspecified"))
      (node (ref "U1") (pin "34") (pinfunction "IO40_34") (pintype "unspecified"))
    )
    (net (code "40") (name "IO41") (class "Default")
      (node (ref "H2") (pin "8") (pinfunction "8_8") (pintype "unspecified"))
      (node (ref "U1") (pin "35") (pinfunction "IO41_35") (pintype "unspecified"))
    )
    (net (code "41") (name "IO42") (class "Default")
      (node (ref "H2") (pin "7") (pinfunction "7_7") (pintype "unspecified"))
      (node (ref "U1") (pin "36") (pinfunction "IO42_36") (pintype "unspecified"))
    )
    (net (code "42") (name "IO45") (class "Default")
      (node (ref "H2") (pin "4") (pinfunction "4_4") (pintype "unspecified"))
      (node (ref "U1") (pin "39") (pinfunction "IO45_39") (pintype "unspecified"))
    )
    (net (code "43") (name "IO46") (class "Default")
      (node (ref "H2") (pin "3") (pinfunction "3_3") (pintype "unspecified"))
      (node (ref "U1") (pin "40") (pinfunction "IO46_40") (pintype "unspecified"))
    )
    (net (code "44") (name "Net-(D5-K)") (class "Default")
      (node (ref "C13") (pin "2") (pinfunction "2_2") (pintype "unspecified"))
      (node (ref "D5") (pin "1") (pinfunction "K_1") (pintype "unspecified"))
      (node (ref "Q3") (pin "3") (pinfunction "S_3") (pintype "unspecified"))
      (node (ref "SW4") (pin "3") (pinfunction "3_3") (pintype "unspecified"))
      (node (ref "U4") (pin "1") (pinfunction "VIN_1") (pintype "unspecified"))
    )
    (net (code "45") (name "Net-(JP1-Pad1)") (class "Default")
      (node (ref "JP1") (pin "1") (pinfunction "1_1") (pintype "unspecified"))
      (node (ref "R18") (pin "2") (pinfunction "2_2") (pintype "unspecified"))
      (node (ref "SW3") (pin "2") (pinfunction "2_2") (pintype "unspecified"))
    )
    (net (code "46") (name "Net-(JP2-Pad3)") (class "Default")
      (node (ref "JP2") (pin "3") (pinfunction "3_3") (pintype "unspecified"))
      (node (ref "R11") (pin "1") (pinfunction "1_1") (pintype "input"))
      (node (ref "R12") (pin "2") (pinfunction "2_2") (pintype "unspecified"))
    )
    (net (code "47") (name "Net-(LED1-DIN)") (class "Default")
      (node (ref "JP3") (pin "1") (pinfunction "1_1") (pintype "unspecified"))
      (node (ref "LED1") (pin "4") (pinfunction "DIN_4") (pintype "unspecified"))
    )
    (net (code "48") (name "Net-(LED2-K)") (class "Default")
      (node (ref "LED2") (pin "1") (pinfunction "K_1") (pintype "unspecified"))
      (node (ref "R17") (pin "2") (pinfunction "2_2") (pintype "unspecified"))
    )
    (net (code "49") (name "Net-(Q1-B)") (class "Default")
      (node (ref "Q1") (pin "1") (pinfunction "B_1") (pintype "unspecified"))
      (node (ref "R5") (pin "2") (pinfunction "2_2") (pintype "unspecified"))
    )
    (net (code "50") (name "Net-(Q2-B)") (class "Default")
      (node (ref "Q2") (pin "1") (pinfunction "B_1") (pintype "unspecified"))
      (node (ref "R6") (pin "2") (pinfunction "2_2") (pintype "unspecified"))
    )
    (net (code "51") (name "Net-(SW4-COM)") (class "Default")
      (node (ref "SW4") (pin "2") (pinfunction "COM_2") (pintype "unspecified"))
      (node (ref "U4") (pin "3") (pinfunction "ENABLE_3") (pintype "unspecified"))
    )
    (net (code "52") (name "Net-(U2-RSTb)") (class "Default")
      (node (ref "R3") (pin "1") (pinfunction "1_1") (pintype "unspecified"))
      (node (ref "U2") (pin "9") (pinfunction "RSTb_9") (pintype "unspecified"))
    )
    (net (code "53") (name "Net-(U2-SUSPENDb)") (class "Default")
      (node (ref "R4") (pin "1") (pinfunction "1_1") (pintype "unspecified"))
      (node (ref "U2") (pin "11") (pinfunction "SUSPENDb_11") (pintype "unspecified"))
    )
    (net (code "54") (name "Net-(U2-VBUS)") (class "Default")
      (node (ref "C5") (pin "1") (pinfunction "1_1") (pintype "unspecified"))
      (node (ref "R1") (pin "2") (pinfunction "2_2") (pintype "unspecified"))
      (node (ref "R2") (pin "2") (pinfunction "2_2") (pintype "unspecified"))
      (node (ref "U2") (pin "8") (pinfunction "VBUS_8") (pintype "unspecified"))
    )
    (net (code "55") (name "Net-(U3-AD0)") (class "Default")
      (node (ref "JP4") (pin "2") (pinfunction "2_2") (pintype "unspecified"))
      (node (ref "U3") (pin "9") (pinfunction "AD0_9") (pintype "unspecified"))
    )
    (net (code "56") (name "Net-(U3-CLKIN)") (class "Default")
      (node (ref "SJ3") (pin "2") (pinfunction "2_2") (pintype "unspecified"))
      (node (ref "U3") (pin "1") (pinfunction "CLKIN_1") (pintype "unspecified"))
    )
    (net (code "57") (name "Net-(U3-CPOUT)") (class "Default")
      (node (ref "C16") (pin "1") (pinfunction "1_1") (pintype "unspecified"))
      (node (ref "U3") (pin "20") (pinfunction "CPOUT_20") (pintype "unspecified"))
    )
    (net (code "58") (name "Net-(U3-FSYNC)") (class "Default")
      (node (ref "SJ2") (pin "2") (pinfunction "2_2") (pintype "unspecified"))
      (node (ref "U3") (pin "11") (pinfunction "FSYNC_11") (pintype "unspecified"))
    )
    (net (code "59") (name "Net-(U3-REGOUT)") (class "Default")
      (node (ref "C17") (pin "2") (pinfunction "2_2") (pintype "unspecified"))
      (node (ref "U3") (pin "10") (pinfunction "REGOUT_10") (pintype "unspecified"))
    )
    (net (code "60") (name "Net-(U5-PROG)") (class "Default")
      (node (ref "R16") (pin "1") (pinfunction "1_1") (pintype "unspecified"))
      (node (ref "U5") (pin "5") (pinfunction "PROG_5") (pintype "unspecified"))
    )
    (net (code "61") (name "Net-(U5-STAT)") (class "Default")
      (node (ref "R17") (pin "1") (pinfunction "1_1") (pintype "unspecified"))
      (node (ref "U5") (pin "1") (pinfunction "STAT_1") (pintype "unspecified"))
    )
    (net (code "62") (name "RTS") (class "Default")
      (node (ref "Q1") (pin "2") (pinfunction "E_2") (pintype "unspecified"))
      (node (ref "R6") (pin "1") (pinfunction "1_1") (pintype "unspecified"))
      (node (ref "U2") (pin "24") (pinfunction "RTS_24") (pintype "unspecified"))
    )
    (net (code "63") (name "RXD0") (class "Default")
      (node (ref "H2") (pin "5") (pinfunction "5_5") (pintype "unspecified"))
      (node (ref "U1") (pin "38") (pinfunction "RXD0_38") (pintype "unspecified"))
      (node (ref "U2") (pin "26") (pinfunction "TXD_26") (pintype "unspecified"))
    )
    (net (code "64") (name "TXD0") (class "Default")
      (node (ref "H2") (pin "6") (pinfunction "6_6") (pintype "unspecified"))
      (node (ref "U1") (pin "37") (pinfunction "TXD0_37") (pintype "unspecified"))
      (node (ref "U2") (pin "25") (pinfunction "RXD_25") (pintype "unspecified"))
    )
    (net (code "65") (name "USB_DN") (class "Default")
      (node (ref "D3") (pin "2") (pinfunction "2_2") (pintype "unspecified"))
      (node (ref "U2") (pin "5") (pinfunction "D-_5") (pintype "unspecified"))
      (node (ref "USB1") (pin "2") (pinfunction "D-_2") (pintype "unspecified"))
    )
    (net (code "66") (name "USB_DP") (class "Default")
      (node (ref "D2") (pin "2") (pinfunction "2_2") (pintype "unspecified"))
      (node (ref "U2") (pin "4") (pinfunction "D+_4") (pintype "unspecified"))
      (node (ref "USB1") (pin "3") (pinfunction "D+_3") (pintype "unspecified"))
    )
    (net (code "67") (name "VBAT") (class "Default")
      (node (ref "C14") (pin "2") (pinfunction "2_2") (pintype "unspecified"))
      (node (ref "CN1") (pin "2") (pinfunction "1_2") (pintype "unspecified"))
      (node (ref "Q3") (pin "2") (pinfunction "D_2") (pintype "unspecified"))
      (node (ref "R11") (pin "2") (pinfunction "2_2") (pintype "input"))
      (node (ref "U5") (pin "3") (pinfunction "VBAT_3") (pintype "unspecified"))
    )
    (net (code "68") (name "VBUS") (class "Default")
      (node (ref "D1") (pin "2") (pinfunction "A_2") (pintype "unspecified"))
      (node (ref "D4") (pin "2") (pinfunction "2_2") (pintype "unspecified"))
      (node (ref "D5") (pin "2") (pinfunction "A_2") (pintype "unspecified"))
      (node (ref "LED2") (pin "2") (pinfunction "A_2") (pintype "unspecified"))
      (node (ref "Q3") (pin "1") (pinfunction "G_1") (pintype "unspecified"))
      (node (ref "R1") (pin "1") (pinfunction "1_1") (pintype "unspecified"))
      (node (ref "R15") (pin "2") (pinfunction "2_2") (pintype "unspecified"))
      (node (ref "U5") (pin "4") (pinfunction "VDD_4") (pintype "unspecified"))
      (node (ref "USB1") (pin "1") (pinfunction "V+_1") (pintype "unspecified"))
      (node (ref "USB2") (pin "1") (pinfunction "V+_1") (pintype "unspecified"))
    )
    (net (code "69") (name "unconnected-(LED1-DOUT-Pad2)") (class "Default")
      (node (ref "LED1") (pin "2") (pinfunction "DOUT_2") (pintype "unspecified+no_connect"))
    )
    (net (code "70") (name "unconnected-(U2-CHR0-Pad15)") (class "Default")
      (node (ref "U2") (pin "15") (pinfunction "CHR0_15") (pintype "unspecified+no_connect"))
    )
    (net (code "71") (name "unconnected-(U2-CHR1-Pad14)") (class "Default")
      (node (ref "U2") (pin "14") (pinfunction "CHR1_14") (pintype "unspecified+no_connect"))
    )
    (net (code "72") (name "unconnected-(U2-CHREN-Pad13)") (class "Default")
      (node (ref "U2") (pin "13") (pinfunction "CHREN_13") (pintype "unspecified+no_connect"))
    )
    (net (code "73") (name "unconnected-(U2-CTS-Pad23)") (class "Default")
      (node (ref "U2") (pin "23") (pinfunction "CTS_23") (pintype "unspecified+no_connect"))
    )
    (net (code "74") (name "unconnected-(U2-DCD-Pad1)") (class "Default")
      (node (ref "U2") (pin "1") (pinfunction "DCD_1") (pintype "unspecified+no_connect"))
    )
    (net (code "75") (name "unconnected-(U2-DSR-Pad27)") (class "Default")
      (node (ref "U2") (pin "27") (pinfunction "DSR_27") (pintype "unspecified+no_connect"))
    )
    (net (code "76") (name "unconnected-(U2-GPIO.0{slash}TXT-Pad19)") (class "Default")
      (node (ref "U2") (pin "19") (pinfunction "GPIO.0/TXT_19") (pintype "unspecified+no_connect"))
    )
    (net (code "77") (name "unconnected-(U2-GPIO.1{slash}RXT-Pad18)") (class "Default")
      (node (ref "U2") (pin "18") (pinfunction "GPIO.1/RXT_18") (pintype "unspecified+no_connect"))
    )
    (net (code "78") (name "unconnected-(U2-GPIO.2{slash}RS485-Pad17)") (class "Default")
      (node (ref "U2") (pin "17") (pinfunction "GPIO.2/RS485_17") (pintype "unspecified+no_connect"))
    )
    (net (code "79") (name "unconnected-(U2-GPIO.3{slash}WAKEUP-Pad16)") (class "Default")
      (node (ref "U2") (pin "16") (pinfunction "GPIO.3/WAKEUP_16") (pintype "unspecified+no_connect"))
    )
    (net (code "80") (name "unconnected-(U2-GPIO.4-Pad22)") (class "Default")
      (node (ref "U2") (pin "22") (pinfunction "GPIO.4_22") (pintype "unspecified+no_connect"))
    )
    (net (code "81") (name "unconnected-(U2-GPIO.5-Pad21)") (class "Default")
      (node (ref "U2") (pin "21") (pinfunction "GPIO.5_21") (pintype "unspecified+no_connect"))
    )
    (net (code "82") (name "unconnected-(U2-GPIO.6-Pad20)") (class "Default")
      (node (ref "U2") (pin "20") (pinfunction "GPIO.6_20") (pintype "unspecified+no_connect"))
    )
    (net (code "83") (name "unconnected-(U2-NC-Pad10)") (class "Default")
      (node (ref "U2") (pin "10") (pinfunction "NC_10") (pintype "unspecified+no_connect"))
    )
    (net (code "84") (name "unconnected-(U2-RI{slash}CLK-Pad2)") (class "Default")
      (node (ref "U2") (pin "2") (pinfunction "RI/CLK_2") (pintype "unspecified+no_connect"))
    )
    (net (code "85") (name "unconnected-(U2-SUSPEND-Pad12)") (class "Default")
      (node (ref "U2") (pin "12") (pinfunction "SUSPEND_12") (pintype "unspecified+no_connect"))
    )
    (net (code "86") (name "unconnected-(U3-AUX_CL-Pad7)") (class "Default")
      (node (ref "U3") (pin "7") (pinfunction "AUX_CL_7") (pintype "unspecified+no_connect"))
    )
    (net (code "87") (name "unconnected-(U3-AUX_DA-Pad6)") (class "Default")
      (node (ref "U3") (pin "6") (pinfunction "AUX_DA_6") (pintype "unspecified+no_connect"))
    )
    (net (code "88") (name "unconnected-(U3-EP-Pad25)") (class "Default")
      (node (ref "U3") (pin "25") (pinfunction "EP_25") (pintype "unspecified+no_connect"))
    )
    (net (code "89") (name "unconnected-(U3-INT-Pad12)") (class "Default")
      (node (ref "U3") (pin "12") (pinfunction "INT_12") (pintype "unspecified+no_connect"))
    )
    (net (code "90") (name "unconnected-(U3-NC-Pad2)") (class "Default")
      (node (ref "U3") (pin "2") (pinfunction "NC_2") (pintype "unspecified+no_connect"))
    )
    (net (code "91") (name "unconnected-(U3-NC-Pad3)") (class "Default")
      (node (ref "U3") (pin "3") (pinfunction "NC_3") (pintype "unspecified+no_connect"))
    )
    (net (code "92") (name "unconnected-(U3-NC-Pad4)") (class "Default")
      (node (ref "U3") (pin "4") (pinfunction "NC_4") (pintype "unspecified+no_connect"))
    )
    (net (code "93") (name "unconnected-(U3-NC-Pad5)") (class "Default")
      (node (ref "U3") (pin "5") (pinfunction "NC_5") (pintype "unspecified+no_connect"))
    )
    (net (code "94") (name "unconnected-(U3-NC-Pad14)") (class "Default")
      (node (ref "U3") (pin "14") (pinfunction "NC_14") (pintype "unspecified+no_connect"))
    )
    (net (code "95") (name "unconnected-(U3-NC-Pad15)") (class "Default")
      (node (ref "U3") (pin "15") (pinfunction "NC_15") (pintype "unspecified+no_connect"))
    )
    (net (code "96") (name "unconnected-(U3-NC-Pad16)") (class "Default")
      (node (ref "U3") (pin "16") (pinfunction "NC_16") (pintype "unspecified+no_connect"))
    )
    (net (code "97") (name "unconnected-(U3-NC-Pad17)") (class "Default")
      (node (ref "U3") (pin "17") (pinfunction "NC_17") (pintype "unspecified+no_connect"))
    )
    (net (code "98") (name "unconnected-(U3-RESV-Pad19)") (class "Default")
      (node (ref "U3") (pin "19") (pinfunction "RESV_19") (pintype "unspecified+no_connect"))
    )
    (net (code "99") (name "unconnected-(U3-RESV-Pad21)") (class "Default")
      (node (ref "U3") (pin "21") (pinfunction "RESV_21") (pintype "unspecified+no_connect"))
    )
    (net (code "100") (name "unconnected-(U3-RESV-Pad22)") (class "Default")
      (node (ref "U3") (pin "22") (pinfunction "RESV_22") (pintype "unspecified+no_connect"))
    )
    (net (code "101") (name "unconnected-(U4-NC-Pad4)") (class "Default")
      (node (ref "U4") (pin "4") (pinfunction "NC_4") (pintype "unspecified+no_connect"))
    )
    (net (code "102") (name "unconnected-(USB1-ID-Pad4)") (class "Default")
      (node (ref "USB1") (pin "4") (pinfunction "ID_4") (pintype "unspecified+no_connect"))
    )
  )
)
